# ESP32_CP2102_USB.net
KiCad netlist of a schematic drawn in Altium Designer
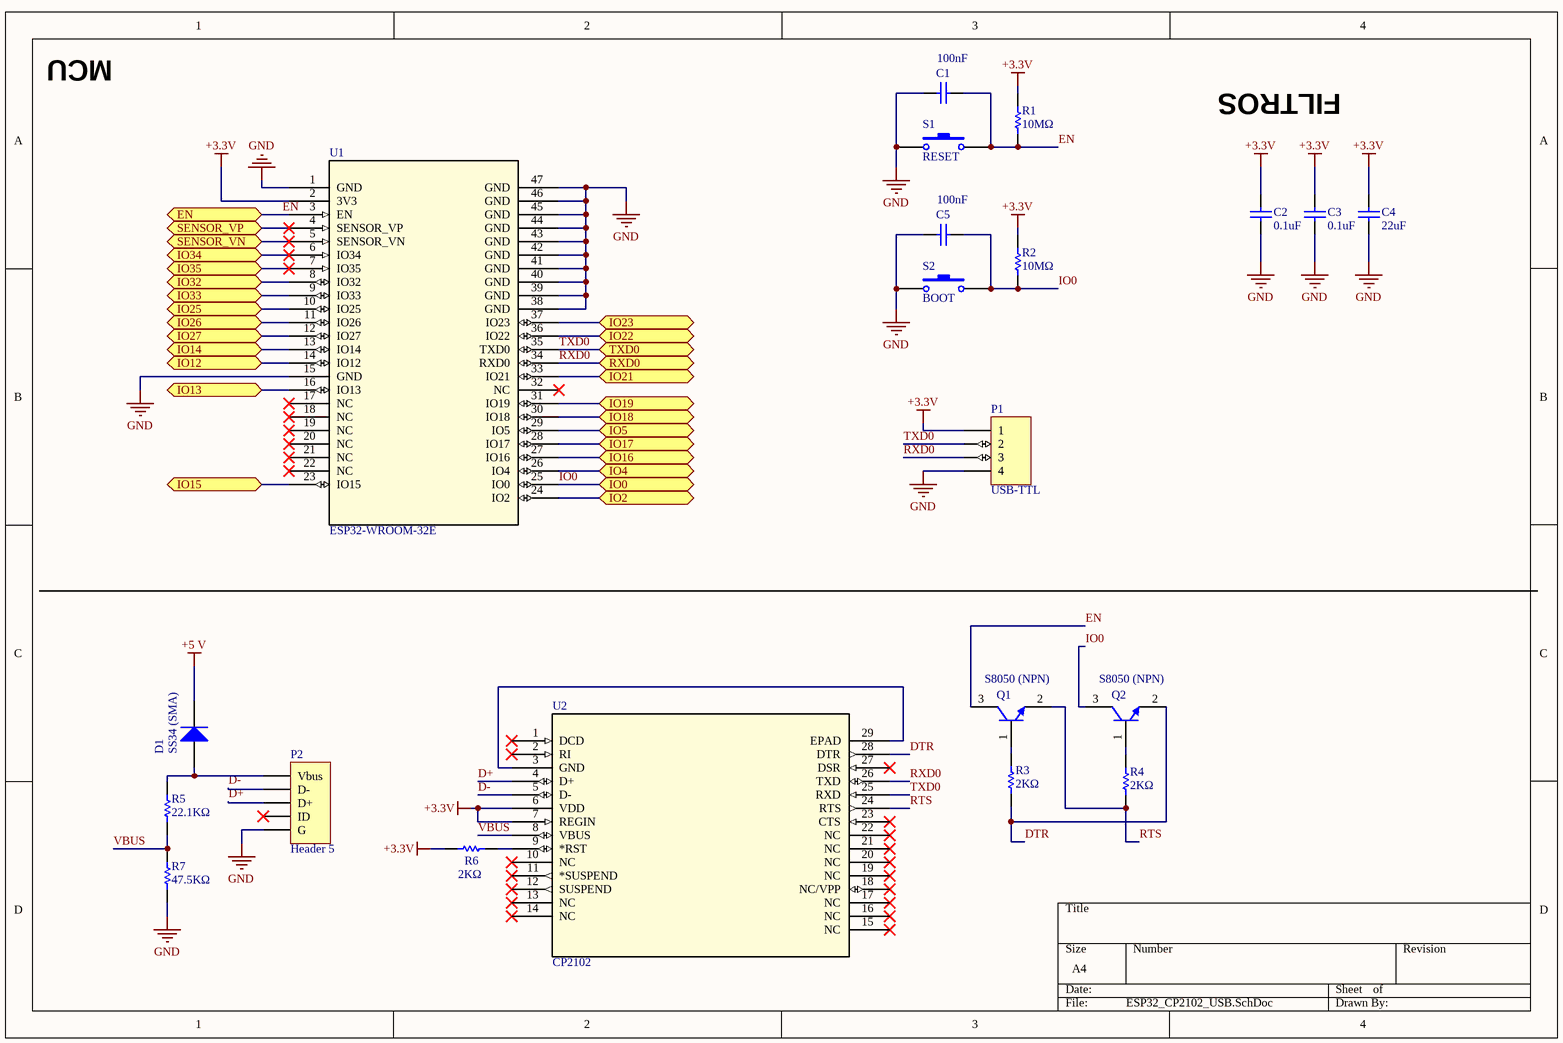
[diagram p0: ESP32_CP2102_USB.SchDoc]

(export (version "E")
  (design (tool "Eeschema 10.0.6"))
  (components
    (comp (ref "C1")
      (value "100nF")
      (footprint "CAPC2012N")
      (description "Capacitor")
      (fields (field (name "PUBLISHER") "Altium Limited"))
      (libsource (lib "Miscellaneous Devices") (part "Cap"))
    )
    (comp (ref "C2")
      (value "0.1uF")
      (footprint "CAPC2012N")
      (description "Capacitor")
      (fields (field (name "PUBLISHER") "Altium Limited"))
      (libsource (lib "Miscellaneous Devices") (part "Cap"))
    )
    (comp (ref "C3")
      (value "0.1uF")
      (footprint "CAPC2012N")
      (description "Capacitor")
      (fields (field (name "PUBLISHER") "Altium Limited"))
      (libsource (lib "Miscellaneous Devices") (part "Cap"))
    )
    (comp (ref "C4")
      (value "22uF")
      (footprint "CAPC2012N")
      (description "Capacitor")
      (fields (field (name "PUBLISHER") "Altium Limited"))
      (libsource (lib "Miscellaneous Devices") (part "Cap"))
    )
    (comp (ref "C5")
      (value "100nF")
      (footprint "CAPC2012N")
      (description "Capacitor")
      (fields (field (name "PUBLISHER") "Altium Limited"))
      (libsource (lib "Miscellaneous Devices") (part "Cap"))
    )
    (comp (ref "D1")
      (value "SS34 (SMA)")
      (footprint "MH_Miscellaneous_Devices_Pcblib:SMA")
      (description "DigiKey: 5399-SS34TR-ND (Encapsulado SMA)")
      (fields (field (name "PUBLISHER") "Altium Limited"))
      (libsource (lib "Miscellaneous Devices") (part "Diode"))
    )
    (comp (ref "P1")
      (value "USB-TTL")
      (footprint "CONNHDR_1X4_2.54MM")
      (description "Header, 4-Pin")
      (fields (field (name "PUBLISHER") "Altium Limited"))
      (libsource (lib "Miscellaneous Connectors") (part "MHDR1X4"))
    )
    (comp (ref "P2")
      (value "Header 5")
      (footprint "ZX62-B-5PA(33)")
      (description "Micro USB Connector")
      (fields (field (name "PUBLISHER") "Altium Limited"))
      (libsource (lib "Miscellaneous Connectors") (part "Header 5"))
    )
    (comp (ref "Q1") (value "S8050 (NPN)") (footprint "S8050") (libsource (lib "MH_Lib") (part "S8050")))
    (comp (ref "Q2") (value "S8050 (NPN)") (footprint "S8050") (libsource (lib "MH_Lib") (part "S8050")))
    (comp (ref "R1")
      (value "10MΩ")
      (footprint "RESC2012N")
      (description "Resistor")
      (fields (field (name "PUBLISHER") "Altium Limited"))
      (libsource (lib "Miscellaneous Devices") (part "Res1"))
    )
    (comp (ref "R2")
      (value "10MΩ")
      (footprint "RESC2012N")
      (description "Resistor")
      (fields (field (name "PUBLISHER") "Altium Limited"))
      (libsource (lib "Miscellaneous Devices") (part "Res1"))
    )
    (comp (ref "R3")
      (value "2KΩ")
      (footprint "RESC2012N")
      (description "Resistor")
      (fields (field (name "PUBLISHER") "Altium Limited"))
      (libsource (lib "Miscellaneous Devices") (part "Res1"))
    )
    (comp (ref "R4")
      (value "2KΩ")
      (footprint "RESC2012N")
      (description "Resistor")
      (fields (field (name "PUBLISHER") "Altium Limited"))
      (libsource (lib "Miscellaneous Devices") (part "Res1"))
    )
    (comp (ref "R5")
      (value "22.1KΩ")
      (footprint "RESC2012N")
      (description "Resistor")
      (fields (field (name "PUBLISHER") "Altium Limited"))
      (libsource (lib "Miscellaneous Devices") (part "Res1"))
    )
    (comp (ref "R6")
      (value "2KΩ")
      (footprint "RESC2012N")
      (description "Resistor")
      (fields (field (name "PUBLISHER") "Altium Limited"))
      (libsource (lib "Miscellaneous Devices") (part "Res1"))
    )
    (comp (ref "R7")
      (value "47.5KΩ")
      (footprint "RESC2012N")
      (description "Resistor")
      (fields (field (name "PUBLISHER") "Altium Limited"))
      (libsource (lib "Miscellaneous Devices") (part "Res1"))
    )
    (comp (ref "S1")
      (value "RESET")
      (footprint "SWITCH TACTILE SPST-NO 0.05A 12V")
      (description "Switch")
      (fields (field (name "PUBLISHER") "Altium Limited"))
      (libsource (lib "Miscellaneous Devices") (part "SW-PB"))
    )
    (comp (ref "S2")
      (value "BOOT")
      (footprint "SWITCH TACTILE SPST-NO 0.05A 12V")
      (description "Switch")
      (fields (field (name "PUBLISHER") "Altium Limited"))
      (libsource (lib "Miscellaneous Devices") (part "SW-PB"))
    )
    (comp (ref "U1")
      (value "ESP32-WROOM-32E")
      (footprint "ESP32-WROOM-32E")
      (libsource (lib "MH_lib") (part "ESP32-WROOM-32E"))
    )
    (comp (ref "U2") (value "CP2102") (footprint "CP2102") (libsource (lib "MH_Lib") (part "CP2102")))
  )
  (nets
    (net (code "1") (name "+3.3V") (class "Default")
      (node (ref "C2") (pin "1") (pinfunction "1_1") (pintype "passive"))
      (node (ref "C3") (pin "1") (pinfunction "1_1") (pintype "passive"))
      (node (ref "C4") (pin "1") (pinfunction "1_1") (pintype "passive"))
      (node (ref "P1") (pin "1") (pinfunction "1_1") (pintype "passive"))
      (node (ref "R1") (pin "2") (pinfunction "2_2") (pintype "passive"))
      (node (ref "R2") (pin "2") (pinfunction "2_2") (pintype "passive"))
      (node (ref "R6") (pin "2") (pinfunction "2_2") (pintype "passive"))
      (node (ref "U1") (pin "2") (pinfunction "3V3_2") (pintype "power_in"))
      (node (ref "U2") (pin "6") (pinfunction "VDD_6") (pintype "power_in"))
      (node (ref "U2") (pin "7") (pinfunction "REGIN_7") (pintype "input"))
    )
    (net (code "2") (name "+5 V") (class "Default")
      (node (ref "D1") (pin "2") (pinfunction "K_2") (pintype "passive"))
    )
    (net (code "3") (name "/D+") (class "Default")
      (node (ref "P2") (pin "3") (pinfunction "D+_3") (pintype "passive"))
      (node (ref "U2") (pin "4") (pinfunction "D+_4") (pintype "bidirectional"))
    )
    (net (code "4") (name "/D-") (class "Default")
      (node (ref "P2") (pin "2") (pinfunction "D-_2") (pintype "passive"))
      (node (ref "U2") (pin "5") (pinfunction "D-_5") (pintype "bidirectional"))
    )
    (net (code "5") (name "/DTR") (class "Default")
      (node (ref "Q2") (pin "2") (pinfunction "E_2") (pintype "passive"))
      (node (ref "R3") (pin "2") (pinfunction "2_2") (pintype "passive"))
      (node (ref "U2") (pin "28") (pinfunction "DTR_28") (pintype "output"))
    )
    (net (code "6") (name "/EN") (class "Default")
      (node (ref "C1") (pin "1") (pinfunction "1_1") (pintype "passive"))
      (node (ref "Q1") (pin "3") (pinfunction "C_3") (pintype "passive"))
      (node (ref "R1") (pin "1") (pinfunction "1_1") (pintype "passive"))
      (node (ref "S1") (pin "2") (pinfunction "2_2") (pintype "passive"))
      (node (ref "U1") (pin "3") (pinfunction "EN_3") (pintype "input"))
    )
    (net (code "7") (name "/IO0") (class "Default")
      (node (ref "C5") (pin "1") (pinfunction "1_1") (pintype "passive"))
      (node (ref "Q2") (pin "3") (pinfunction "C_3") (pintype "passive"))
      (node (ref "R2") (pin "1") (pinfunction "1_1") (pintype "passive"))
      (node (ref "S2") (pin "2") (pinfunction "2_2") (pintype "passive"))
      (node (ref "U1") (pin "25") (pinfunction "IO0_25") (pintype "bidirectional"))
    )
    (net (code "8") (name "/IO2") (class "Default")
      (node (ref "U1") (pin "24") (pinfunction "IO2_24") (pintype "bidirectional"))
    )
    (net (code "9") (name "/IO4") (class "Default")
      (node (ref "U1") (pin "26") (pinfunction "IO4_26") (pintype "bidirectional"))
    )
    (net (code "10") (name "/IO5") (class "Default")
      (node (ref "U1") (pin "29") (pinfunction "IO5_29") (pintype "bidirectional"))
    )
    (net (code "11") (name "/IO12") (class "Default")
      (node (ref "U1") (pin "14") (pinfunction "IO12_14") (pintype "bidirectional"))
    )
    (net (code "12") (name "/IO13") (class "Default")
      (node (ref "U1") (pin "16") (pinfunction "IO13_16") (pintype "bidirectional"))
    )
    (net (code "13") (name "/IO14") (class "Default")
      (node (ref "U1") (pin "13") (pinfunction "IO14_13") (pintype "bidirectional"))
    )
    (net (code "14") (name "/IO15") (class "Default")
      (node (ref "U1") (pin "23") (pinfunction "IO15_23") (pintype "bidirectional"))
    )
    (net (code "15") (name "/IO16") (class "Default")
      (node (ref "U1") (pin "27") (pinfunction "IO16_27") (pintype "bidirectional"))
    )
    (net (code "16") (name "/IO17") (class "Default")
      (node (ref "U1") (pin "28") (pinfunction "IO17_28") (pintype "bidirectional"))
    )
    (net (code "17") (name "/IO18") (class "Default")
      (node (ref "U1") (pin "30") (pinfunction "IO18_30") (pintype "bidirectional"))
    )
    (net (code "18") (name "/IO19") (class "Default")
      (node (ref "U1") (pin "31") (pinfunction "IO19_31") (pintype "bidirectional"))
    )
    (net (code "19") (name "/IO21") (class "Default")
      (node (ref "U1") (pin "33") (pinfunction "IO21_33") (pintype "bidirectional"))
    )
    (net (code "20") (name "/IO22") (class "Default")
      (node (ref "U1") (pin "36") (pinfunction "IO22_36") (pintype "bidirectional"))
    )
    (net (code "21") (name "/IO23") (class "Default")
      (node (ref "U1") (pin "37") (pinfunction "IO23_37") (pintype "bidirectional"))
    )
    (net (code "22") (name "/IO25") (class "Default")
      (node (ref "U1") (pin "10") (pinfunction "IO25_10") (pintype "bidirectional"))
    )
    (net (code "23") (name "/IO26") (class "Default")
      (node (ref "U1") (pin "11") (pinfunction "IO26_11") (pintype "bidirectional"))
    )
    (net (code "24") (name "/IO27") (class "Default")
      (node (ref "U1") (pin "12") (pinfunction "IO27_12") (pintype "bidirectional"))
    )
    (net (code "25") (name "/IO32") (class "Default")
      (node (ref "U1") (pin "8") (pinfunction "IO32_8") (pintype "bidirectional"))
    )
    (net (code "26") (name "/IO33") (class "Default")
      (node (ref "U1") (pin "9") (pinfunction "IO33_9") (pintype "bidirectional"))
    )
    (net (code "27") (name "/IO34") (class "Default")
      (node (ref "U1") (pin "6") (pinfunction "IO34_6") (pintype "input+no_connect"))
    )
    (net (code "28") (name "/IO35") (class "Default")
      (node (ref "U1") (pin "7") (pinfunction "IO35_7") (pintype "input+no_connect"))
    )
    (net (code "29") (name "/RTS") (class "Default")
      (node (ref "Q1") (pin "2") (pinfunction "E_2") (pintype "passive"))
      (node (ref "R4") (pin "1") (pinfunction "1_1") (pintype "passive"))
      (node (ref "U2") (pin "24") (pinfunction "RTS_24") (pintype "output"))
    )
    (net (code "30") (name "/RXD0") (class "Default")
      (node (ref "P1") (pin "3") (pinfunction "3_3") (pintype "bidirectional"))
      (node (ref "U1") (pin "34") (pinfunction "RXD0_34") (pintype "bidirectional"))
      (node (ref "U2") (pin "26") (pinfunction "TXD_26") (pintype "bidirectional"))
    )
    (net (code "31") (name "/SENSOR_VN") (class "Default")
      (node (ref "U1") (pin "5") (pinfunction "SENSOR_VN_5") (pintype "input+no_connect"))
    )
    (net (code "32") (name "/SENSOR_VP") (class "Default")
      (node (ref "U1") (pin "4") (pinfunction "SENSOR_VP_4") (pintype "input+no_connect"))
    )
    (net (code "33") (name "/TXD0") (class "Default")
      (node (ref "P1") (pin "2") (pinfunction "2_2") (pintype "bidirectional"))
      (node (ref "U1") (pin "35") (pinfunction "TXD0_35") (pintype "bidirectional"))
      (node (ref "U2") (pin "25") (pinfunction "RXD_25") (pintype "input"))
    )
    (net (code "34") (name "/VBUS") (class "Default")
      (node (ref "R5") (pin "2") (pinfunction "2_2") (pintype "passive"))
      (node (ref "R7") (pin "1") (pinfunction "1_1") (pintype "passive"))
      (node (ref "U2") (pin "8") (pinfunction "VBUS_8") (pintype "bidirectional"))
    )
    (net (code "35") (name "GND") (class "Default")
      (node (ref "C1") (pin "2") (pinfunction "2_2") (pintype "passive"))
      (node (ref "C2") (pin "2") (pinfunction "2_2") (pintype "passive"))
      (node (ref "C3") (pin "2") (pinfunction "2_2") (pintype "passive"))
      (node (ref "C4") (pin "2") (pinfunction "2_2") (pintype "passive"))
      (node (ref "C5") (pin "2") (pinfunction "2_2") (pintype "passive"))
      (node (ref "P1") (pin "4") (pinfunction "4_4") (pintype "passive"))
      (node (ref "P2") (pin "5") (pinfunction "G_5") (pintype "passive"))
      (node (ref "R7") (pin "2") (pinfunction "2_2") (pintype "passive"))
      (node (ref "S1") (pin "1") (pinfunction "1_1") (pintype "passive"))
      (node (ref "S2") (pin "1") (pinfunction "1_1") (pintype "passive"))
      (node (ref "U1") (pin "1") (pinfunction "GND_1") (pintype "power_in"))
      (node (ref "U1") (pin "15") (pinfunction "GND_15") (pintype "power_in"))
      (node (ref "U1") (pin "38") (pinfunction "GND_38") (pintype "power_in"))
      (node (ref "U1") (pin "39") (pinfunction "GND_39") (pintype "power_in"))
      (node (ref "U1") (pin "40") (pinfunction "GND_40") (pintype "power_in"))
      (node (ref "U1") (pin "41") (pinfunction "GND_41") (pintype "power_in"))
      (node (ref "U1") (pin "42") (pinfunction "GND_42") (pintype "power_in"))
      (node (ref "U1") (pin "43") (pinfunction "GND_43") (pintype "power_in"))
      (node (ref "U1") (pin "44") (pinfunction "GND_44") (pintype "power_in"))
      (node (ref "U1") (pin "45") (pinfunction "GND_45") (pintype "power_in"))
      (node (ref "U1") (pin "46") (pinfunction "GND_46") (pintype "power_in"))
      (node (ref "U1") (pin "47") (pinfunction "GND_47") (pintype "power_in"))
    )
    (net (code "36") (name "Net-(D1-A)") (class "Default")
      (node (ref "D1") (pin "1") (pinfunction "A_1") (pintype "passive"))
      (node (ref "P2") (pin "1") (pinfunction "Vbus_1") (pintype "passive"))
      (node (ref "R5") (pin "1") (pinfunction "1_1") (pintype "passive"))
    )
    (net (code "37") (name "Net-(Q1-B)") (class "Default")
      (node (ref "Q1") (pin "1") (pinfunction "B_1") (pintype "passive"))
      (node (ref "R3") (pin "1") (pinfunction "1_1") (pintype "passive"))
    )
    (net (code "38") (name "Net-(Q2-B)") (class "Default")
      (node (ref "Q2") (pin "1") (pinfunction "B_1") (pintype "passive"))
      (node (ref "R4") (pin "2") (pinfunction "2_2") (pintype "passive"))
    )
    (net (code "39") (name "Net-(U2-*RST)") (class "Default")
      (node (ref "R6") (pin "1") (pinfunction "1_1") (pintype "passive"))
      (node (ref "U2") (pin "9") (pinfunction "*RST_9") (pintype "bidirectional"))
    )
    (net (code "40") (name "Net-(U2-EPAD)") (class "Default")
      (node (ref "U2") (pin "29") (pinfunction "EPAD_29") (pintype "passive"))
      (node (ref "U2") (pin "3") (pinfunction "GND_3") (pintype "power_in"))
    )
    (net (code "41") (name "unconnected-(P2-ID-Pad4)") (class "Default")
      (node (ref "P2") (pin "4") (pinfunction "ID_4") (pintype "passive+no_connect"))
    )
    (net (code "42") (name "unconnected-(U1-NC-Pad17)") (class "Default")
      (node (ref "U1") (pin "17") (pinfunction "NC_17") (pintype "passive+no_connect"))
    )
    (net (code "43") (name "unconnected-(U1-NC-Pad18)") (class "Default")
      (node (ref "U1") (pin "18") (pinfunction "NC_18") (pintype "passive+no_connect"))
    )
    (net (code "44") (name "unconnected-(U1-NC-Pad19)") (class "Default")
      (node (ref "U1") (pin "19") (pinfunction "NC_19") (pintype "passive+no_connect"))
    )
    (net (code "45") (name "unconnected-(U1-NC-Pad20)") (class "Default")
      (node (ref "U1") (pin "20") (pinfunction "NC_20") (pintype "passive+no_connect"))
    )
    (net (code "46") (name "unconnected-(U1-NC-Pad21)") (class "Default")
      (node (ref "U1") (pin "21") (pinfunction "NC_21") (pintype "passive+no_connect"))
    )
    (net (code "47") (name "unconnected-(U1-NC-Pad22)") (class "Default")
      (node (ref "U1") (pin "22") (pinfunction "NC_22") (pintype "passive+no_connect"))
    )
    (net (code "48") (name "unconnected-(U1-NC-Pad32)") (class "Default")
      (node (ref "U1") (pin "32") (pinfunction "NC_32") (pintype "passive+no_connect"))
    )
    (net (code "49") (name "unconnected-(U2-*SUSPEND-Pad11)") (class "Default")
      (node (ref "U2") (pin "11") (pinfunction "*SUSPEND_11") (pintype "output+no_connect"))
    )
    (net (code "50") (name "unconnected-(U2-CTS-Pad23)") (class "Default")
      (node (ref "U2") (pin "23") (pinfunction "CTS_23") (pintype "input+no_connect"))
    )
    (net (code "51") (name "unconnected-(U2-DCD-Pad1)") (class "Default")
      (node (ref "U2") (pin "1") (pinfunction "DCD_1") (pintype "input+no_connect"))
    )
    (net (code "52") (name "unconnected-(U2-DSR-Pad27)") (class "Default")
      (node (ref "U2") (pin "27") (pinfunction "DSR_27") (pintype "input+no_connect"))
    )
    (net (code "53") (name "unconnected-(U2-NC-Pad10)") (class "Default")
      (node (ref "U2") (pin "10") (pinfunction "NC_10") (pintype "passive+no_connect"))
    )
    (net (code "54") (name "unconnected-(U2-NC-Pad13)") (class "Default")
      (node (ref "U2") (pin "13") (pinfunction "NC_13") (pintype "passive+no_connect"))
    )
    (net (code "55") (name "unconnected-(U2-NC-Pad14)") (class "Default")
      (node (ref "U2") (pin "14") (pinfunction "NC_14") (pintype "passive+no_connect"))
    )
    (net (code "56") (name "unconnected-(U2-NC-Pad15)") (class "Default")
      (node (ref "U2") (pin "15") (pinfunction "NC_15") (pintype "passive+no_connect"))
    )
    (net (code "57") (name "unconnected-(U2-NC-Pad16)") (class "Default")
      (node (ref "U2") (pin "16") (pinfunction "NC_16") (pintype "passive+no_connect"))
    )
    (net (code "58") (name "unconnected-(U2-NC-Pad17)") (class "Default")
      (node (ref "U2") (pin "17") (pinfunction "NC_17") (pintype "passive+no_connect"))
    )
    (net (code "59") (name "unconnected-(U2-NC-Pad19)") (class "Default")
      (node (ref "U2") (pin "19") (pinfunction "NC_19") (pintype "passive+no_connect"))
    )
    (net (code "60") (name "unconnected-(U2-NC-Pad20)") (class "Default")
      (node (ref "U2") (pin "20") (pinfunction "NC_20") (pintype "passive+no_connect"))
    )
    (net (code "61") (name "unconnected-(U2-NC-Pad21)") (class "Default")
      (node (ref "U2") (pin "21") (pinfunction "NC_21") (pintype "passive+no_connect"))
    )
    (net (code "62") (name "unconnected-(U2-NC-Pad22)") (class "Default")
      (node (ref "U2") (pin "22") (pinfunction "NC_22") (pintype "passive+no_connect"))
    )
    (net (code "63") (name "unconnected-(U2-NC{slash}VPP-Pad18)") (class "Default")
      (node (ref "U2") (pin "18") (pinfunction "NC/VPP_18") (pintype "bidirectional+no_connect"))
    )
    (net (code "64") (name "unconnected-(U2-RI-Pad2)") (class "Default")
      (node (ref "U2") (pin "2") (pinfunction "RI_2") (pintype "input+no_connect"))
    )
    (net (code "65") (name "unconnected-(U2-SUSPEND-Pad12)") (class "Default")
      (node (ref "U2") (pin "12") (pinfunction "SUSPEND_12") (pintype "output+no_connect"))
    )
  )
)
